# MCB-K64F-v1_0_0.net
KiCad netlist of a schematic drawn in EAGLE
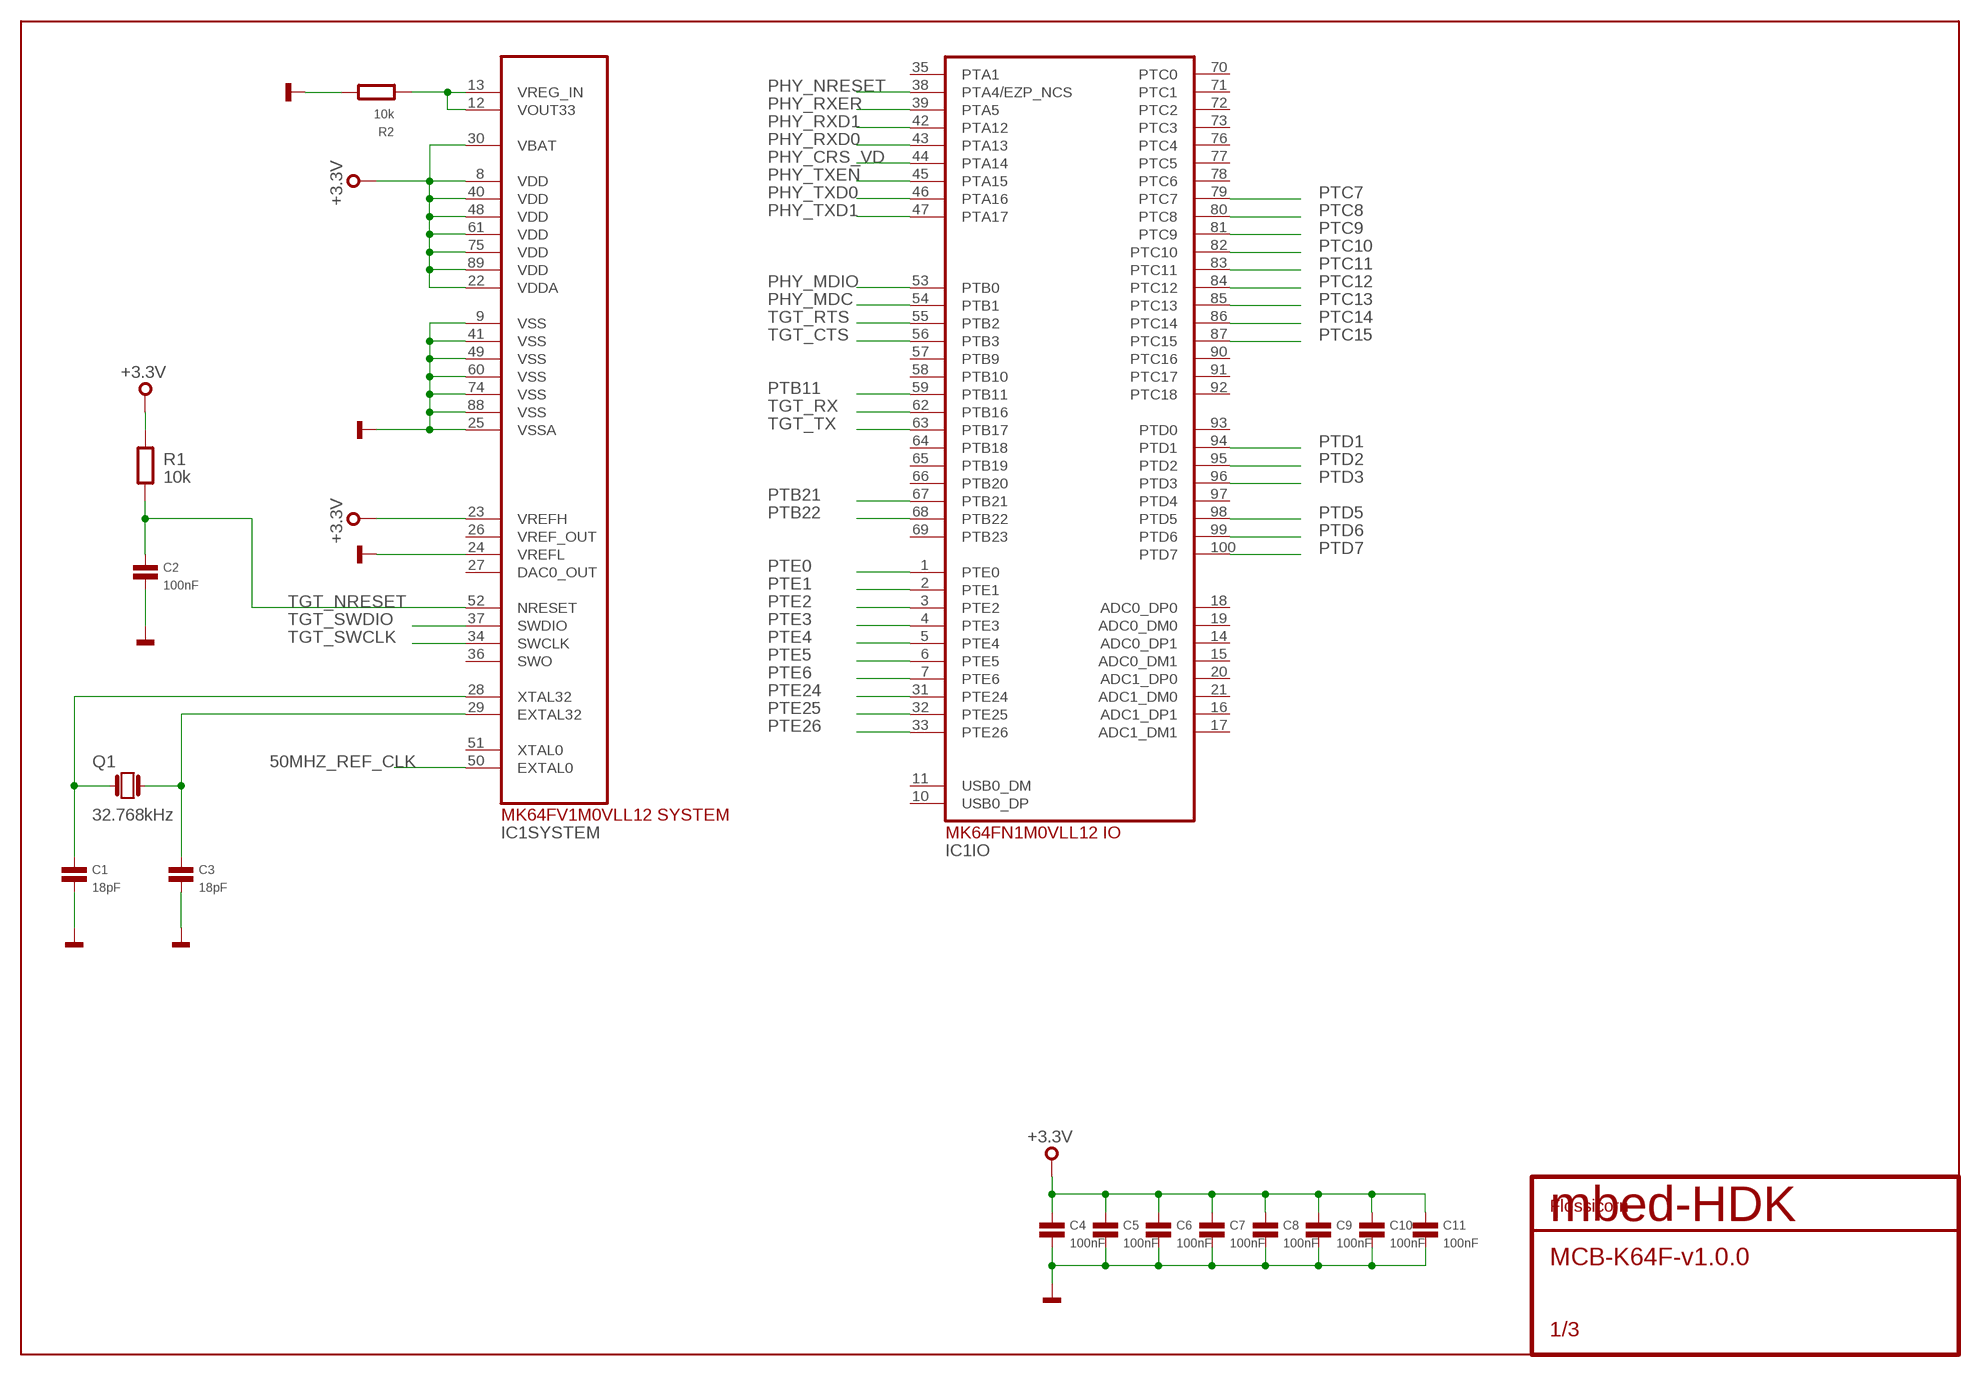
[diagram p0: schematic, sheet 1]
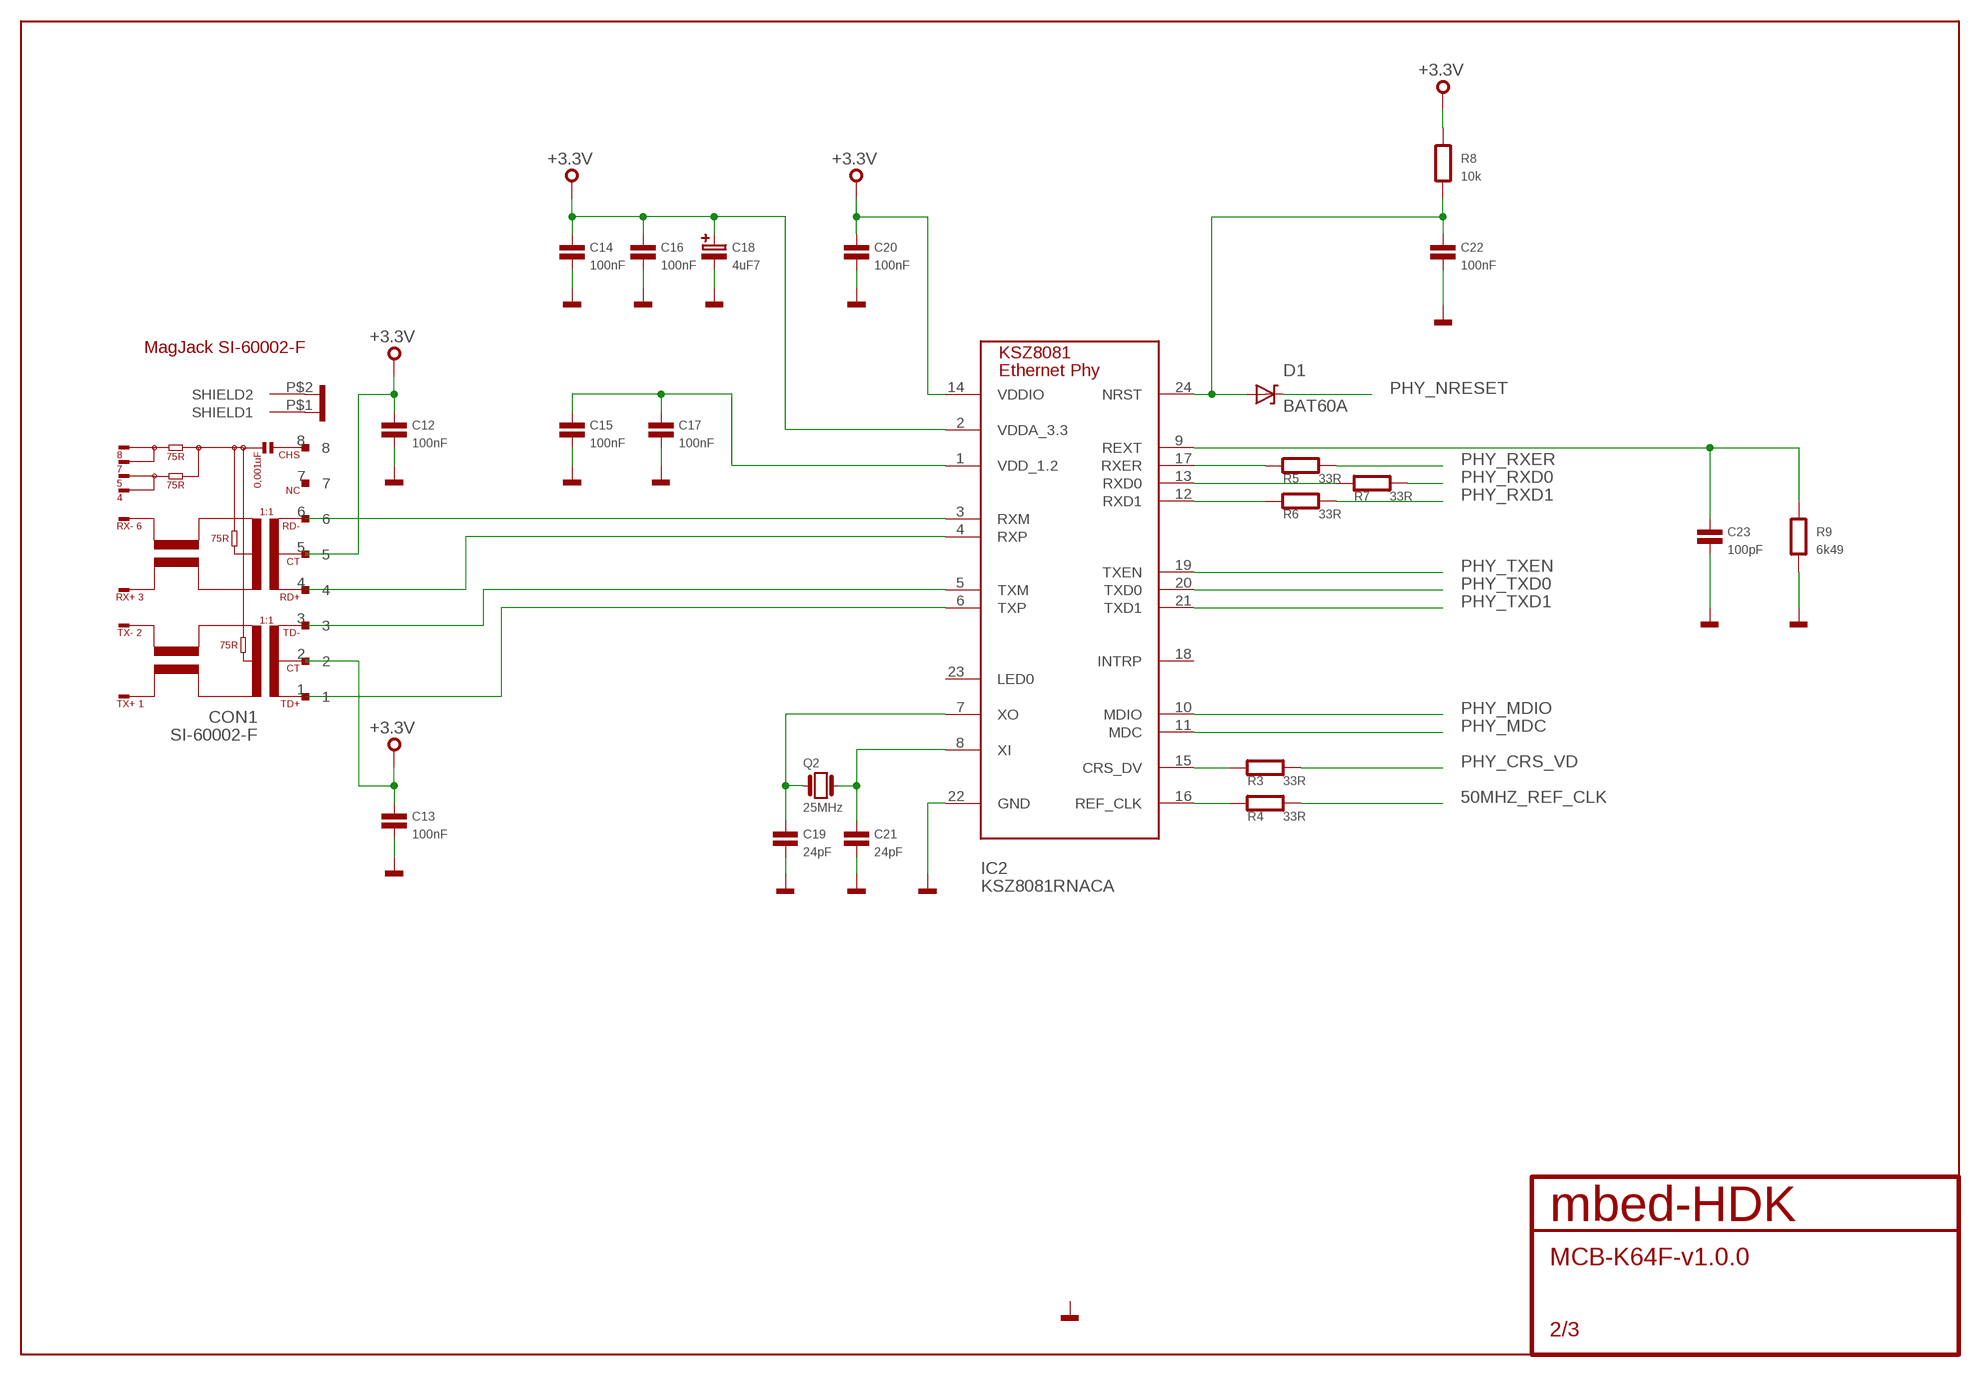
[diagram p1: schematic, sheet 2]
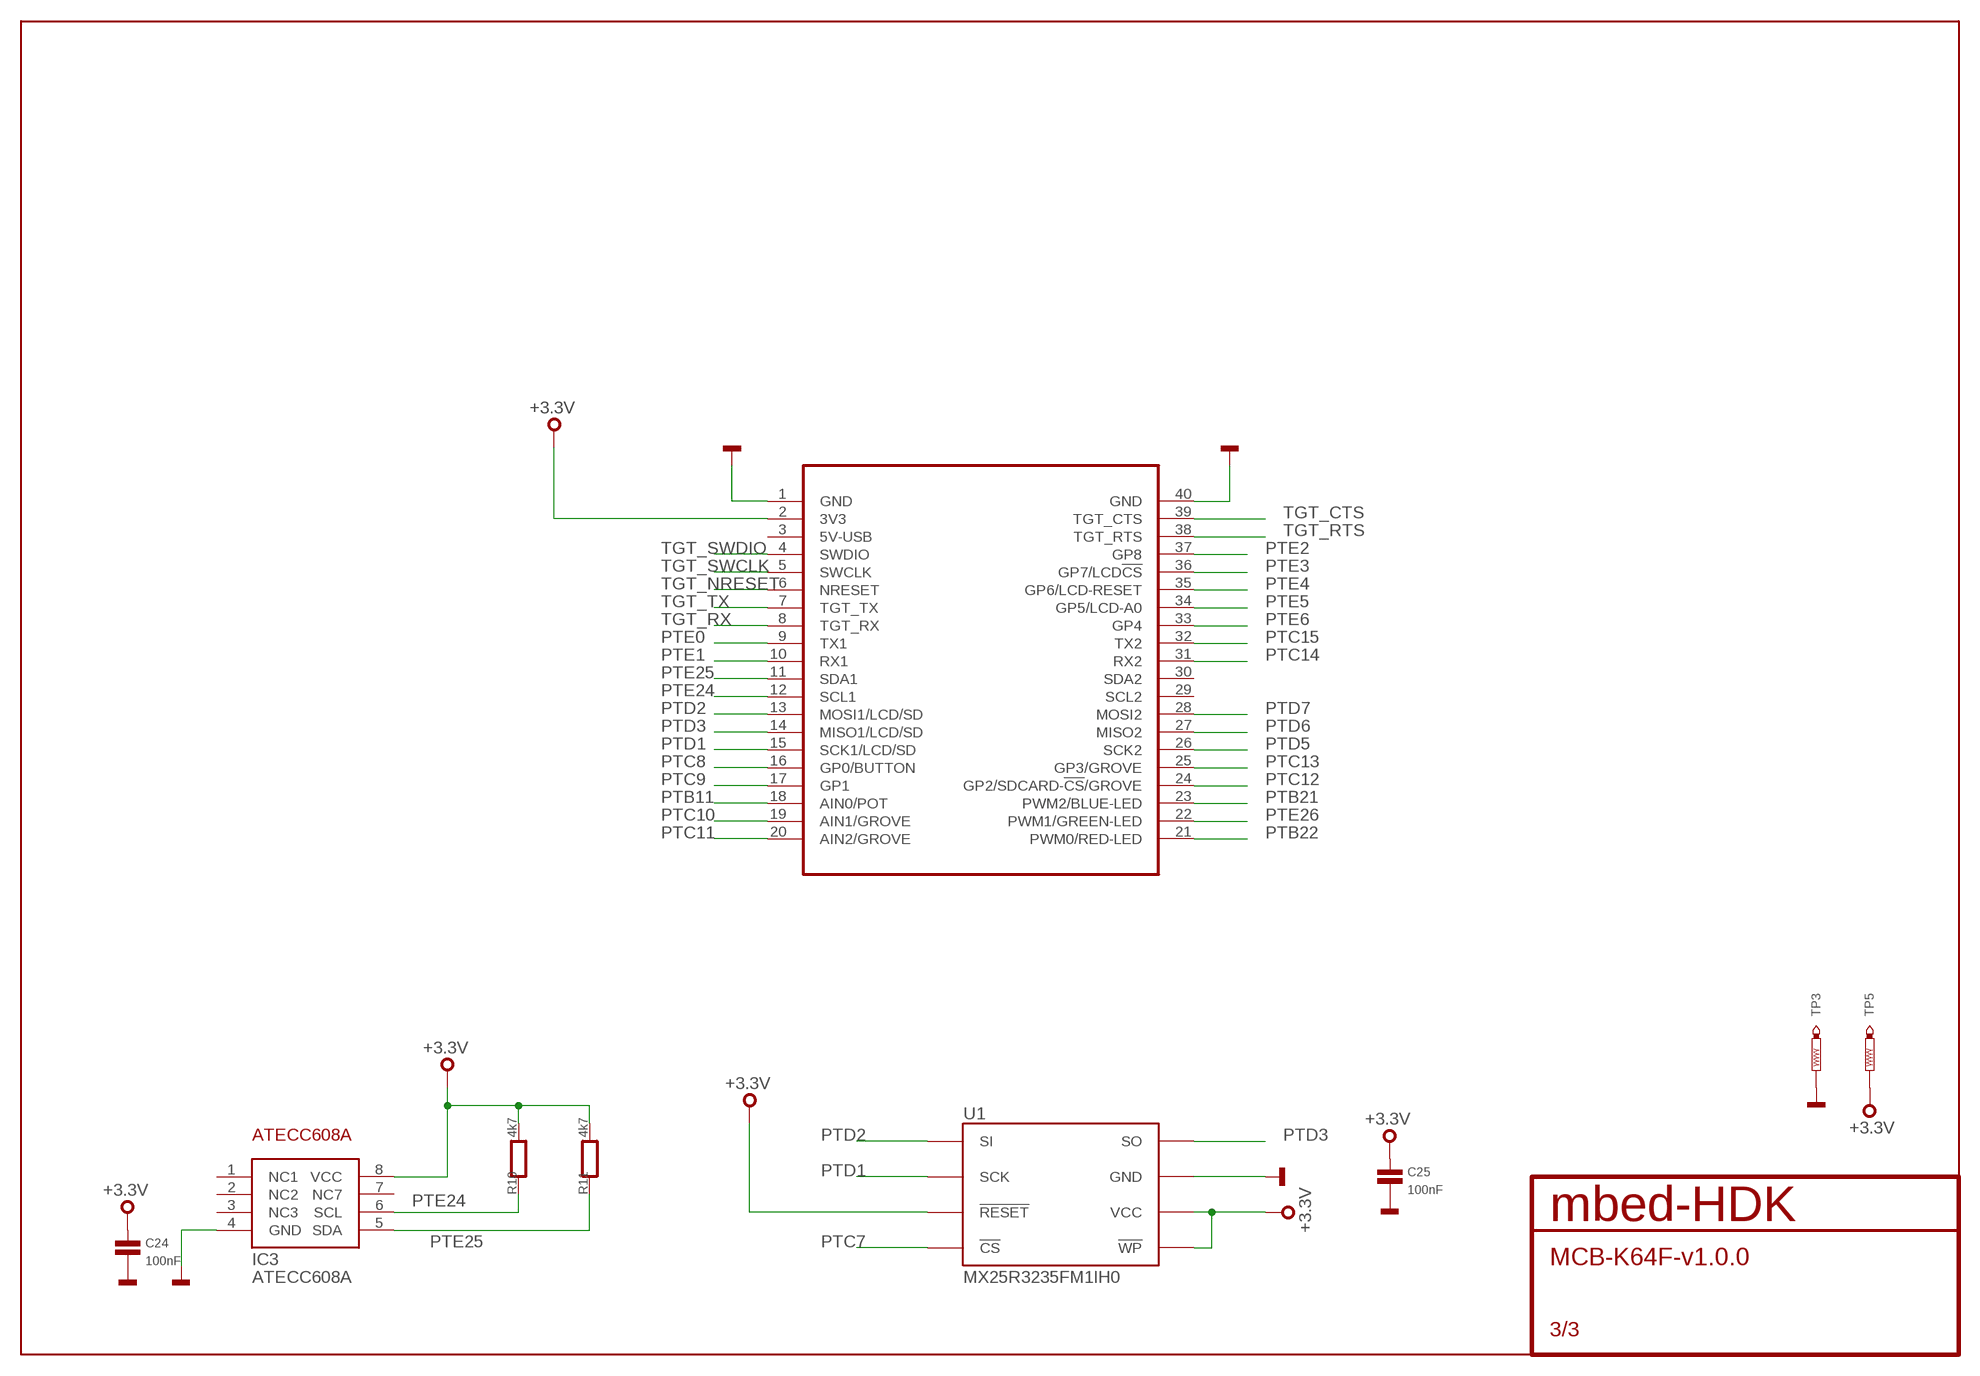
[diagram p2: schematic, sheet 3]

(export (version "E")
  (design (tool "Eeschema 10.0.6"))
  (components
    (comp (ref "C12")
      (value "100nF")
      (footprint "eagle-import:0603")
      (libsource (lib "eagle-import") (part "C0603"))
    )
    (comp (ref "C13")
      (value "100nF")
      (footprint "eagle-import:0603")
      (libsource (lib "eagle-import") (part "C0603"))
    )
    (comp (ref "C14")
      (value "100nF")
      (footprint "eagle-import:0603")
      (libsource (lib "eagle-import") (part "C0603"))
    )
    (comp (ref "C15")
      (value "100nF")
      (footprint "eagle-import:0603")
      (libsource (lib "eagle-import") (part "C0603"))
    )
    (comp (ref "C16")
      (value "100nF")
      (footprint "eagle-import:0603")
      (libsource (lib "eagle-import") (part "C0603"))
    )
    (comp (ref "C17")
      (value "100nF")
      (footprint "eagle-import:0603")
      (libsource (lib "eagle-import") (part "C0603"))
    )
    (comp (ref "C18")
      (value "4uF7")
      (footprint "eagle-import:SMC_A")
      (libsource (lib "eagle-import") (part "C-POLA"))
    )
    (comp (ref "C19")
      (value "24pF")
      (footprint "eagle-import:0603")
      (libsource (lib "eagle-import") (part "C0603"))
    )
    (comp (ref "C20")
      (value "100nF")
      (footprint "eagle-import:0603")
      (libsource (lib "eagle-import") (part "C0603"))
    )
    (comp (ref "C21")
      (value "24pF")
      (footprint "eagle-import:0603")
      (libsource (lib "eagle-import") (part "C0603"))
    )
    (comp (ref "C22")
      (value "100nF")
      (footprint "eagle-import:0603")
      (libsource (lib "eagle-import") (part "C0603"))
    )
    (comp (ref "C23")
      (value "100pF")
      (footprint "eagle-import:0603")
      (libsource (lib "eagle-import") (part "C0603"))
    )
    (comp (ref "CON1")
      (value "SI-60002-F")
      (footprint "eagle-import:RJ45")
      (fields (field (name "MF") "Stewart Connector"))
      (libsource (lib "eagle-import") (part "SI-60002-F"))
    )
    (comp (ref "D1")
      (value "BAT60A")
      (footprint "eagle-import:BAT60A")
      (libsource (lib "eagle-import") (part "BAT60A"))
    )
    (comp (ref "IC2")
      (value "KSZ8081RNACA")
      (footprint "eagle-import:QFN-24")
      (libsource (lib "eagle-import") (part "KSZ8081RNACA"))
    )
    (comp (ref "Q2")
      (value "25MHz")
      (footprint "eagle-import:3.2X.2.5")
      (libsource (lib "eagle-import") (part "Q_3.2X2.5"))
    )
    (comp (ref "R3")
      (value "33R")
      (footprint "eagle-import:0603")
      (libsource (lib "eagle-import") (part "R0603"))
    )
    (comp (ref "R4")
      (value "33R")
      (footprint "eagle-import:0603")
      (libsource (lib "eagle-import") (part "R0603"))
    )
    (comp (ref "R5")
      (value "33R")
      (footprint "eagle-import:0603")
      (libsource (lib "eagle-import") (part "R0603"))
    )
    (comp (ref "R6")
      (value "33R")
      (footprint "eagle-import:0603")
      (libsource (lib "eagle-import") (part "R0603"))
    )
    (comp (ref "R7")
      (value "33R")
      (footprint "eagle-import:0603")
      (libsource (lib "eagle-import") (part "R0603"))
    )
    (comp (ref "R8")
      (value "10k")
      (footprint "eagle-import:0603")
      (libsource (lib "eagle-import") (part "R0603"))
    )
    (comp (ref "R9")
      (value "6k49")
      (footprint "eagle-import:0603")
      (libsource (lib "eagle-import") (part "R0603"))
    )
    (comp (ref "C1")
      (value "18pF")
      (footprint "eagle-import:0603")
      (libsource (lib "eagle-import") (part "C0603"))
    )
    (comp (ref "C2")
      (value "100nF")
      (footprint "eagle-import:0603")
      (libsource (lib "eagle-import") (part "C0603"))
    )
    (comp (ref "C3")
      (value "18pF")
      (footprint "eagle-import:0603")
      (libsource (lib "eagle-import") (part "C0603"))
    )
    (comp (ref "C4")
      (value "100nF")
      (footprint "eagle-import:0603")
      (libsource (lib "eagle-import") (part "C0603"))
    )
    (comp (ref "C5")
      (value "100nF")
      (footprint "eagle-import:0603")
      (libsource (lib "eagle-import") (part "C0603"))
    )
    (comp (ref "C6")
      (value "100nF")
      (footprint "eagle-import:0603")
      (libsource (lib "eagle-import") (part "C0603"))
    )
    (comp (ref "C7")
      (value "100nF")
      (footprint "eagle-import:0603")
      (libsource (lib "eagle-import") (part "C0603"))
    )
    (comp (ref "C8")
      (value "100nF")
      (footprint "eagle-import:0603")
      (libsource (lib "eagle-import") (part "C0603"))
    )
    (comp (ref "C9")
      (value "100nF")
      (footprint "eagle-import:0603")
      (libsource (lib "eagle-import") (part "C0603"))
    )
    (comp (ref "C10")
      (value "100nF")
      (footprint "eagle-import:0603")
      (libsource (lib "eagle-import") (part "C0603"))
    )
    (comp (ref "C11")
      (value "100nF")
      (footprint "eagle-import:0603")
      (libsource (lib "eagle-import") (part "C0603"))
    )
    (comp (ref "IC1")
      (value "MK64FN1M0VLL12")
      (footprint "eagle-import:LQFP100")
      (libsource (lib "eagle-import") (part "MK64FN1M0VLL12"))
    )
    (comp (ref "Q1")
      (value "32.768kHz")
      (footprint "eagle-import:FC135")
      (libsource (lib "eagle-import") (part "Q_FC135"))
    )
    (comp (ref "R1")
      (value "10k")
      (footprint "eagle-import:0603")
      (libsource (lib "eagle-import") (part "R0603"))
    )
    (comp (ref "R2")
      (value "10k")
      (footprint "eagle-import:0603")
      (libsource (lib "eagle-import") (part "R0603"))
    )
    (comp (ref "SS1")
      (value "FLOSSICORN0.5")
      (footprint "eagle-import:FLOSSICORN-0.5")
      (libsource (lib "eagle-import") (part "FLOSSICORN0.5"))
    )
    (comp (ref "C24")
      (value "100nF")
      (footprint "eagle-import:0603")
      (libsource (lib "eagle-import") (part "CAPACITOR0603"))
    )
    (comp (ref "C25")
      (value "100nF")
      (footprint "eagle-import:0603")
      (libsource (lib "eagle-import") (part "CAPACITOR0603"))
    )
    (comp (ref "IC3")
      (value "ATECC608A")
      (footprint "eagle-import:SO8")
      (libsource (lib "eagle-import") (part "ATECC608A"))
    )
    (comp (ref "MOD1")
      (value "MODULE_DAUGHTER")
      (footprint "eagle-import:MODULE_DAUGHTER")
      (libsource (lib "eagle-import") (part "MODULE_DAUGHTER"))
    )
    (comp (ref "R10")
      (value "4k7")
      (footprint "eagle-import:0603")
      (libsource (lib "eagle-import") (part "RESISTOR0603"))
    )
    (comp (ref "R11")
      (value "4k7")
      (footprint "eagle-import:0603")
      (libsource (lib "eagle-import") (part "RESISTOR0603"))
    )
    (comp (ref "TP3")
      (value "TEST-POINT-50R-PTH")
      (footprint "eagle-import:TP50-PTH")
      (libsource (lib "eagle-import") (part "TEST-POINT-50R-PTH"))
    )
    (comp (ref "TP5")
      (value "TEST-POINT-50R-PTH")
      (footprint "eagle-import:TP50-PTH")
      (libsource (lib "eagle-import") (part "TEST-POINT-50R-PTH"))
    )
    (comp (ref "U1")
      (value "MX25R3235FM1IH0")
      (footprint "eagle-import:SO8")
      (fields (field (name "MF") "Macronix"))
      (libsource (lib "eagle-import") (part "MX25R3235FM1IH0"))
    )
  )
  (nets
    (net (code "1") (name "+3.3V") (class "Default")
      (node (ref "C10") (pin "1") (pinfunction "P$1_1") (pintype "passive"))
      (node (ref "C11") (pin "1") (pinfunction "P$1_1") (pintype "passive"))
      (node (ref "C12") (pin "1") (pinfunction "P$1_1") (pintype "passive"))
      (node (ref "C13") (pin "1") (pinfunction "P$1_1") (pintype "passive"))
      (node (ref "C14") (pin "1") (pinfunction "P$1_1") (pintype "passive"))
      (node (ref "C16") (pin "1") (pinfunction "P$1_1") (pintype "passive"))
      (node (ref "C18") (pin "+") (pinfunction "+_+") (pintype "passive"))
      (node (ref "C20") (pin "1") (pinfunction "P$1_1") (pintype "passive"))
      (node (ref "C24") (pin "1") (pinfunction "P$1_1") (pintype "passive"))
      (node (ref "C25") (pin "1") (pinfunction "P$1_1") (pintype "passive"))
      (node (ref "C4") (pin "1") (pinfunction "P$1_1") (pintype "passive"))
      (node (ref "C5") (pin "1") (pinfunction "P$1_1") (pintype "passive"))
      (node (ref "C6") (pin "1") (pinfunction "P$1_1") (pintype "passive"))
      (node (ref "C7") (pin "1") (pinfunction "P$1_1") (pintype "passive"))
      (node (ref "C8") (pin "1") (pinfunction "P$1_1") (pintype "passive"))
      (node (ref "C9") (pin "1") (pinfunction "P$1_1") (pintype "passive"))
      (node (ref "CON1") (pin "2") (pinfunction "2_2") (pintype "passive"))
      (node (ref "CON1") (pin "5") (pinfunction "5_5") (pintype "passive"))
      (node (ref "IC1") (pin "22") (pinfunction "VDDA_22") (pintype "bidirectional"))
      (node (ref "IC1") (pin "23") (pinfunction "VREFH_23") (pintype "bidirectional"))
      (node (ref "IC1") (pin "30") (pinfunction "VBAT_30") (pintype "bidirectional"))
      (node (ref "IC1") (pin "40") (pinfunction "VDD_40") (pintype "bidirectional"))
      (node (ref "IC1") (pin "48") (pinfunction "VDD_48") (pintype "bidirectional"))
      (node (ref "IC1") (pin "61") (pinfunction "VDD_61") (pintype "bidirectional"))
      (node (ref "IC1") (pin "75") (pinfunction "VDD_75") (pintype "bidirectional"))
      (node (ref "IC1") (pin "8") (pinfunction "VDD_8") (pintype "bidirectional"))
      (node (ref "IC1") (pin "89") (pinfunction "VDD_89") (pintype "bidirectional"))
      (node (ref "IC2") (pin "14") (pinfunction "VDDIO_14") (pintype "bidirectional"))
      (node (ref "IC2") (pin "2") (pinfunction "VDDA_3.3_2") (pintype "bidirectional"))
      (node (ref "IC3") (pin "8") (pinfunction "VCC_8") (pintype "bidirectional"))
      (node (ref "MOD1") (pin "2") (pinfunction "3V3_2") (pintype "bidirectional"))
      (node (ref "R1") (pin "2") (pinfunction "P$2_2") (pintype "passive"))
      (node (ref "R10") (pin "2") (pinfunction "P$2_2") (pintype "passive"))
      (node (ref "R11") (pin "2") (pinfunction "P$2_2") (pintype "passive"))
      (node (ref "R8") (pin "2") (pinfunction "P$2_2") (pintype "passive"))
      (node (ref "TP5") (pin "TP") (pinfunction "TP_TP") (pintype "input"))
      (node (ref "U1") (pin "3") (pinfunction "~{WP}_3") (pintype "bidirectional"))
      (node (ref "U1") (pin "7") (pinfunction "~{RESET}_7") (pintype "bidirectional"))
      (node (ref "U1") (pin "8") (pinfunction "VCC_8") (pintype "bidirectional"))
    )
    (net (code "2") (name "50MHZ_REF_CLK") (class "Default")
      (node (ref "IC1") (pin "50") (pinfunction "EXTAL0_50") (pintype "bidirectional"))
      (node (ref "R4") (pin "2") (pinfunction "P$2_2") (pintype "passive"))
    )
    (net (code "3") (name "GND") (class "Default")
      (node (ref "C1") (pin "2") (pinfunction "P$2_2") (pintype "passive"))
      (node (ref "C10") (pin "2") (pinfunction "P$2_2") (pintype "passive"))
      (node (ref "C11") (pin "2") (pinfunction "P$2_2") (pintype "passive"))
      (node (ref "C12") (pin "2") (pinfunction "P$2_2") (pintype "passive"))
      (node (ref "C13") (pin "2") (pinfunction "P$2_2") (pintype "passive"))
      (node (ref "C14") (pin "2") (pinfunction "P$2_2") (pintype "passive"))
      (node (ref "C15") (pin "2") (pinfunction "P$2_2") (pintype "passive"))
      (node (ref "C16") (pin "2") (pinfunction "P$2_2") (pintype "passive"))
      (node (ref "C17") (pin "2") (pinfunction "P$2_2") (pintype "passive"))
      (node (ref "C18") (pin "-") (pinfunction "-_-") (pintype "passive"))
      (node (ref "C19") (pin "2") (pinfunction "P$2_2") (pintype "passive"))
      (node (ref "C2") (pin "2") (pinfunction "P$2_2") (pintype "passive"))
      (node (ref "C20") (pin "2") (pinfunction "P$2_2") (pintype "passive"))
      (node (ref "C21") (pin "2") (pinfunction "P$2_2") (pintype "passive"))
      (node (ref "C22") (pin "2") (pinfunction "P$2_2") (pintype "passive"))
      (node (ref "C23") (pin "2") (pinfunction "P$2_2") (pintype "passive"))
      (node (ref "C24") (pin "2") (pinfunction "P$2_2") (pintype "passive"))
      (node (ref "C25") (pin "2") (pinfunction "P$2_2") (pintype "passive"))
      (node (ref "C3") (pin "2") (pinfunction "P$2_2") (pintype "passive"))
      (node (ref "C4") (pin "2") (pinfunction "P$2_2") (pintype "passive"))
      (node (ref "C5") (pin "2") (pinfunction "P$2_2") (pintype "passive"))
      (node (ref "C6") (pin "2") (pinfunction "P$2_2") (pintype "passive"))
      (node (ref "C7") (pin "2") (pinfunction "P$2_2") (pintype "passive"))
      (node (ref "C8") (pin "2") (pinfunction "P$2_2") (pintype "passive"))
      (node (ref "C9") (pin "2") (pinfunction "P$2_2") (pintype "passive"))
      (node (ref "CON1") (pin "P$1") (pinfunction "SHIELD1_P$1") (pintype "bidirectional"))
      (node (ref "CON1") (pin "P$2") (pinfunction "SHIELD2_P$2") (pintype "bidirectional"))
      (node (ref "IC1") (pin "24") (pinfunction "VREFL_24") (pintype "bidirectional"))
      (node (ref "IC1") (pin "25") (pinfunction "VSSA_25") (pintype "bidirectional"))
      (node (ref "IC1") (pin "41") (pinfunction "VSS_41") (pintype "bidirectional"))
      (node (ref "IC1") (pin "49") (pinfunction "VSS_49") (pintype "bidirectional"))
      (node (ref "IC1") (pin "60") (pinfunction "VSS_60") (pintype "bidirectional"))
      (node (ref "IC1") (pin "74") (pinfunction "VSS_74") (pintype "bidirectional"))
      (node (ref "IC1") (pin "88") (pinfunction "VSS_88") (pintype "bidirectional"))
      (node (ref "IC1") (pin "9") (pinfunction "VSS_9") (pintype "bidirectional"))
      (node (ref "IC2") (pin "22") (pinfunction "GND_22") (pintype "bidirectional"))
      (node (ref "IC3") (pin "4") (pinfunction "GND_4") (pintype "bidirectional"))
      (node (ref "MOD1") (pin "1") (pinfunction "GND_1") (pintype "bidirectional"))
      (node (ref "MOD1") (pin "40") (pinfunction "GND_40") (pintype "bidirectional"))
      (node (ref "R2") (pin "2") (pinfunction "P$2_2") (pintype "passive"))
      (node (ref "R9") (pin "1") (pinfunction "P$1_1") (pintype "passive"))
      (node (ref "TP3") (pin "TP") (pinfunction "TP_TP") (pintype "input"))
      (node (ref "U1") (pin "4") (pinfunction "GND_4") (pintype "bidirectional"))
    )
    (net (code "4") (name "Net-(C1-P$1)") (class "Default")
      (node (ref "C1") (pin "1") (pinfunction "P$1_1") (pintype "passive"))
      (node (ref "IC1") (pin "28") (pinfunction "XTAL32_28") (pintype "bidirectional"))
      (node (ref "Q1") (pin "X1") (pinfunction "1_X1") (pintype "passive"))
    )
    (net (code "5") (name "Net-(C3-P$1)") (class "Default")
      (node (ref "C3") (pin "1") (pinfunction "P$1_1") (pintype "passive"))
      (node (ref "IC1") (pin "29") (pinfunction "EXTAL32_29") (pintype "bidirectional"))
      (node (ref "Q1") (pin "X2") (pinfunction "2_X2") (pintype "passive"))
    )
    (net (code "6") (name "Net-(C15-P$1)") (class "Default")
      (node (ref "C15") (pin "1") (pinfunction "P$1_1") (pintype "passive"))
      (node (ref "C17") (pin "1") (pinfunction "P$1_1") (pintype "passive"))
      (node (ref "IC2") (pin "1") (pinfunction "VDD_1.2_1") (pintype "bidirectional"))
    )
    (net (code "7") (name "Net-(C19-P$1)") (class "Default")
      (node (ref "C19") (pin "1") (pinfunction "P$1_1") (pintype "passive"))
      (node (ref "IC2") (pin "7") (pinfunction "XO_7") (pintype "bidirectional"))
      (node (ref "Q2") (pin "P$1") (pinfunction "1_P$1") (pintype "passive"))
    )
    (net (code "8") (name "Net-(C21-P$1)") (class "Default")
      (node (ref "C21") (pin "1") (pinfunction "P$1_1") (pintype "passive"))
      (node (ref "IC2") (pin "8") (pinfunction "XI_8") (pintype "bidirectional"))
      (node (ref "Q2") (pin "P$3") (pinfunction "2_P$3") (pintype "passive"))
    )
    (net (code "9") (name "Net-(C22-P$1)") (class "Default")
      (node (ref "C22") (pin "1") (pinfunction "P$1_1") (pintype "passive"))
      (node (ref "D1") (pin "A") (pinfunction "A_A") (pintype "passive"))
      (node (ref "IC2") (pin "24") (pinfunction "NRST_24") (pintype "bidirectional"))
      (node (ref "R8") (pin "1") (pinfunction "P$1_1") (pintype "passive"))
    )
    (net (code "10") (name "Net-(C23-P$1)") (class "Default")
      (node (ref "C23") (pin "1") (pinfunction "P$1_1") (pintype "passive"))
      (node (ref "IC2") (pin "9") (pinfunction "REXT_9") (pintype "bidirectional"))
      (node (ref "R9") (pin "2") (pinfunction "P$2_2") (pintype "passive"))
    )
    (net (code "11") (name "Net-(IC1B-VOUT33)") (class "Default")
      (node (ref "IC1") (pin "12") (pinfunction "VOUT33_12") (pintype "bidirectional"))
      (node (ref "IC1") (pin "13") (pinfunction "VREG_IN_13") (pintype "bidirectional"))
      (node (ref "R2") (pin "1") (pinfunction "P$1_1") (pintype "passive"))
    )
    (net (code "12") (name "Net-(IC2-CRS_DV)") (class "Default")
      (node (ref "IC2") (pin "15") (pinfunction "CRS_DV_15") (pintype "bidirectional"))
      (node (ref "R3") (pin "1") (pinfunction "P$1_1") (pintype "passive"))
    )
    (net (code "13") (name "Net-(IC2-REF_CLK)") (class "Default")
      (node (ref "IC2") (pin "16") (pinfunction "REF_CLK_16") (pintype "bidirectional"))
      (node (ref "R4") (pin "1") (pinfunction "P$1_1") (pintype "passive"))
    )
    (net (code "14") (name "Net-(IC2-RXD0)") (class "Default")
      (node (ref "IC2") (pin "13") (pinfunction "RXD0_13") (pintype "bidirectional"))
      (node (ref "R7") (pin "1") (pinfunction "P$1_1") (pintype "passive"))
    )
    (net (code "15") (name "Net-(IC2-RXD1)") (class "Default")
      (node (ref "IC2") (pin "12") (pinfunction "RXD1_12") (pintype "bidirectional"))
      (node (ref "R6") (pin "1") (pinfunction "P$1_1") (pintype "passive"))
    )
    (net (code "16") (name "Net-(IC2-RXER)") (class "Default")
      (node (ref "IC2") (pin "17") (pinfunction "RXER_17") (pintype "bidirectional"))
      (node (ref "R5") (pin "1") (pinfunction "P$1_1") (pintype "passive"))
    )
    (net (code "17") (name "Net-(IC2-RXM)") (class "Default")
      (node (ref "CON1") (pin "6") (pinfunction "6_6") (pintype "passive"))
      (node (ref "IC2") (pin "3") (pinfunction "RXM_3") (pintype "bidirectional"))
    )
    (net (code "18") (name "Net-(IC2-RXP)") (class "Default")
      (node (ref "CON1") (pin "4") (pinfunction "4_4") (pintype "passive"))
      (node (ref "IC2") (pin "4") (pinfunction "RXP_4") (pintype "bidirectional"))
    )
    (net (code "19") (name "Net-(IC2-TXM)") (class "Default")
      (node (ref "CON1") (pin "3") (pinfunction "3_3") (pintype "passive"))
      (node (ref "IC2") (pin "5") (pinfunction "TXM_5") (pintype "bidirectional"))
    )
    (net (code "20") (name "Net-(IC2-TXP)") (class "Default")
      (node (ref "CON1") (pin "1") (pinfunction "1_1") (pintype "passive"))
      (node (ref "IC2") (pin "6") (pinfunction "TXP_6") (pintype "bidirectional"))
    )
    (net (code "21") (name "PHY_CRS_VD") (class "Default")
      (node (ref "IC1") (pin "44") (pinfunction "PTA14_44") (pintype "bidirectional"))
      (node (ref "R3") (pin "2") (pinfunction "P$2_2") (pintype "passive"))
    )
    (net (code "22") (name "PHY_MDC") (class "Default")
      (node (ref "IC1") (pin "54") (pinfunction "PTB1_54") (pintype "bidirectional"))
      (node (ref "IC2") (pin "11") (pinfunction "MDC_11") (pintype "bidirectional"))
    )
    (net (code "23") (name "PHY_MDIO") (class "Default")
      (node (ref "IC1") (pin "53") (pinfunction "PTB0_53") (pintype "bidirectional"))
      (node (ref "IC2") (pin "10") (pinfunction "MDIO_10") (pintype "bidirectional"))
    )
    (net (code "24") (name "PHY_NRESET") (class "Default")
      (node (ref "D1") (pin "K") (pinfunction "K_K") (pintype "passive"))
      (node (ref "IC1") (pin "38") (pinfunction "PTA4/EZP_NCS_38") (pintype "bidirectional"))
    )
    (net (code "25") (name "PHY_RXD0") (class "Default")
      (node (ref "IC1") (pin "43") (pinfunction "PTA13_43") (pintype "bidirectional"))
      (node (ref "R7") (pin "2") (pinfunction "P$2_2") (pintype "passive"))
    )
    (net (code "26") (name "PHY_RXD1") (class "Default")
      (node (ref "IC1") (pin "42") (pinfunction "PTA12_42") (pintype "bidirectional"))
      (node (ref "R6") (pin "2") (pinfunction "P$2_2") (pintype "passive"))
    )
    (net (code "27") (name "PHY_RXER") (class "Default")
      (node (ref "IC1") (pin "39") (pinfunction "PTA5_39") (pintype "bidirectional"))
      (node (ref "R5") (pin "2") (pinfunction "P$2_2") (pintype "passive"))
    )
    (net (code "28") (name "PHY_TXD0") (class "Default")
      (node (ref "IC1") (pin "46") (pinfunction "PTA16_46") (pintype "bidirectional"))
      (node (ref "IC2") (pin "20") (pinfunction "TXD0_20") (pintype "bidirectional"))
    )
    (net (code "29") (name "PHY_TXD1") (class "Default")
      (node (ref "IC1") (pin "47") (pinfunction "PTA17_47") (pintype "bidirectional"))
      (node (ref "IC2") (pin "21") (pinfunction "TXD1_21") (pintype "bidirectional"))
    )
    (net (code "30") (name "PHY_TXEN") (class "Default")
      (node (ref "IC1") (pin "45") (pinfunction "PTA15_45") (pintype "bidirectional"))
      (node (ref "IC2") (pin "19") (pinfunction "TXEN_19") (pintype "bidirectional"))
    )
    (net (code "31") (name "PTB11") (class "Default")
      (node (ref "IC1") (pin "59") (pinfunction "PTB11_59") (pintype "bidirectional"))
      (node (ref "MOD1") (pin "18") (pinfunction "AIN0/POT_18") (pintype "bidirectional"))
    )
    (net (code "32") (name "PTB21") (class "Default")
      (node (ref "IC1") (pin "67") (pinfunction "PTB21_67") (pintype "bidirectional"))
      (node (ref "MOD1") (pin "23") (pinfunction "PWM2/BLUE-LED_23") (pintype "bidirectional"))
    )
    (net (code "33") (name "PTB22") (class "Default")
      (node (ref "IC1") (pin "68") (pinfunction "PTB22_68") (pintype "bidirectional"))
      (node (ref "MOD1") (pin "21") (pinfunction "PWM0/RED-LED_21") (pintype "bidirectional"))
    )
    (net (code "34") (name "PTC7") (class "Default")
      (node (ref "IC1") (pin "79") (pinfunction "PTC7_79") (pintype "bidirectional"))
      (node (ref "U1") (pin "1") (pinfunction "~{CS}_1") (pintype "bidirectional"))
    )
    (net (code "35") (name "PTC8") (class "Default")
      (node (ref "IC1") (pin "80") (pinfunction "PTC8_80") (pintype "bidirectional"))
      (node (ref "MOD1") (pin "16") (pinfunction "GP0/BUTTON_16") (pintype "bidirectional"))
    )
    (net (code "36") (name "PTC9") (class "Default")
      (node (ref "IC1") (pin "81") (pinfunction "PTC9_81") (pintype "bidirectional"))
      (node (ref "MOD1") (pin "17") (pinfunction "GP1_17") (pintype "bidirectional"))
    )
    (net (code "37") (name "PTC10") (class "Default")
      (node (ref "IC1") (pin "82") (pinfunction "PTC10_82") (pintype "bidirectional"))
      (node (ref "MOD1") (pin "19") (pinfunction "AIN1/GROVE_19") (pintype "bidirectional"))
    )
    (net (code "38") (name "PTC11") (class "Default")
      (node (ref "IC1") (pin "83") (pinfunction "PTC11_83") (pintype "bidirectional"))
      (node (ref "MOD1") (pin "20") (pinfunction "AIN2/GROVE_20") (pintype "bidirectional"))
    )
    (net (code "39") (name "PTC12") (class "Default")
      (node (ref "IC1") (pin "84") (pinfunction "PTC12_84") (pintype "bidirectional"))
      (node (ref "MOD1") (pin "24") (pinfunction "GP2/SDCARD-~{CS}/GROVE_24") (pintype "bidirectional"))
    )
    (net (code "40") (name "PTC13") (class "Default")
      (node (ref "IC1") (pin "85") (pinfunction "PTC13_85") (pintype "bidirectional"))
      (node (ref "MOD1") (pin "25") (pinfunction "GP3/GROVE_25") (pintype "bidirectional"))
    )
    (net (code "41") (name "PTC14") (class "Default")
      (node (ref "IC1") (pin "86") (pinfunction "PTC14_86") (pintype "bidirectional"))
      (node (ref "MOD1") (pin "31") (pinfunction "RX2_31") (pintype "bidirectional"))
    )
    (net (code "42") (name "PTC15") (class "Default")
      (node (ref "IC1") (pin "87") (pinfunction "PTC15_87") (pintype "bidirectional"))
      (node (ref "MOD1") (pin "32") (pinfunction "TX2_32") (pintype "bidirectional"))
    )
    (net (code "43") (name "PTD1") (class "Default")
      (node (ref "IC1") (pin "94") (pinfunction "PTD1_94") (pintype "bidirectional"))
      (node (ref "MOD1") (pin "15") (pinfunction "SCK1/LCD/SD_15") (pintype "bidirectional"))
      (node (ref "U1") (pin "6") (pinfunction "SCK_6") (pintype "bidirectional"))
    )
    (net (code "44") (name "PTD2") (class "Default")
      (node (ref "IC1") (pin "95") (pinfunction "PTD2_95") (pintype "bidirectional"))
      (node (ref "MOD1") (pin "13") (pinfunction "MOSI1/LCD/SD_13") (pintype "bidirectional"))
      (node (ref "U1") (pin "5") (pinfunction "SI_5") (pintype "bidirectional"))
    )
    (net (code "45") (name "PTD3") (class "Default")
      (node (ref "IC1") (pin "96") (pinfunction "PTD3_96") (pintype "bidirectional"))
      (node (ref "MOD1") (pin "14") (pinfunction "MISO1/LCD/SD_14") (pintype "bidirectional"))
      (node (ref "U1") (pin "2") (pinfunction "SO_2") (pintype "bidirectional"))
    )
    (net (code "46") (name "PTD5") (class "Default")
      (node (ref "IC1") (pin "98") (pinfunction "PTD5_98") (pintype "bidirectional"))
      (node (ref "MOD1") (pin "26") (pinfunction "SCK2_26") (pintype "bidirectional"))
    )
    (net (code "47") (name "PTD6") (class "Default")
      (node (ref "IC1") (pin "99") (pinfunction "PTD6_99") (pintype "bidirectional"))
      (node (ref "MOD1") (pin "27") (pinfunction "MISO2_27") (pintype "bidirectional"))
    )
    (net (code "48") (name "PTD7") (class "Default")
      (node (ref "IC1") (pin "100") (pinfunction "PTD7_100") (pintype "bidirectional"))
      (node (ref "MOD1") (pin "28") (pinfunction "MOSI2_28") (pintype "bidirectional"))
    )
    (net (code "49") (name "PTE0") (class "Default")
      (node (ref "IC1") (pin "1") (pinfunction "PTE0_1") (pintype "bidirectional"))
      (node (ref "MOD1") (pin "9") (pinfunction "TX1_9") (pintype "bidirectional"))
    )
    (net (code "50") (name "PTE1") (class "Default")
      (node (ref "IC1") (pin "2") (pinfunction "PTE1_2") (pintype "bidirectional"))
      (node (ref "MOD1") (pin "10") (pinfunction "RX1_10") (pintype "bidirectional"))
    )
    (net (code "51") (name "PTE2") (class "Default")
      (node (ref "IC1") (pin "3") (pinfunction "PTE2_3") (pintype "bidirectional"))
      (node (ref "MOD1") (pin "37") (pinfunction "GP8_37") (pintype "bidirectional"))
    )
    (net (code "52") (name "PTE3") (class "Default")
      (node (ref "IC1") (pin "4") (pinfunction "PTE3_4") (pintype "bidirectional"))
      (node (ref "MOD1") (pin "36") (pinfunction "GP7/LCD~{CS}_36") (pintype "bidirectional"))
    )
    (net (code "53") (name "PTE4") (class "Default")
      (node (ref "IC1") (pin "5") (pinfunction "PTE4_5") (pintype "bidirectional"))
      (node (ref "MOD1") (pin "35") (pinfunction "GP6/LCD-RESET_35") (pintype "bidirectional"))
    )
    (net (code "54") (name "PTE5") (class "Default")
      (node (ref "IC1") (pin "6") (pinfunction "PTE5_6") (pintype "bidirectional"))
      (node (ref "MOD1") (pin "34") (pinfunction "GP5/LCD-A0_34") (pintype "bidirectional"))
    )
    (net (code "55") (name "PTE6") (class "Default")
      (node (ref "IC1") (pin "7") (pinfunction "PTE6_7") (pintype "bidirectional"))
      (node (ref "MOD1") (pin "33") (pinfunction "GP4_33") (pintype "bidirectional"))
    )
    (net (code "56") (name "PTE24") (class "Default")
      (node (ref "IC1") (pin "31") (pinfunction "PTE24_31") (pintype "bidirectional"))
      (node (ref "IC3") (pin "6") (pinfunction "SCL_6") (pintype "bidirectional"))
      (node (ref "MOD1") (pin "12") (pinfunction "SCL1_12") (pintype "bidirectional"))
      (node (ref "R10") (pin "1") (pinfunction "P$1_1") (pintype "passive"))
    )
    (net (code "57") (name "PTE25") (class "Default")
      (node (ref "IC1") (pin "32") (pinfunction "PTE25_32") (pintype "bidirectional"))
      (node (ref "IC3") (pin "5") (pinfunction "SDA_5") (pintype "bidirectional"))
      (node (ref "MOD1") (pin "11") (pinfunction "SDA1_11") (pintype "bidirectional"))
      (node (ref "R11") (pin "1") (pinfunction "P$1_1") (pintype "passive"))
    )
    (net (code "58") (name "PTE26") (class "Default")
      (node (ref "IC1") (pin "33") (pinfunction "PTE26_33") (pintype "bidirectional"))
      (node (ref "MOD1") (pin "22") (pinfunction "PWM1/GREEN-LED_22") (pintype "bidirectional"))
    )
    (net (code "59") (name "TGT_CTS") (class "Default")
      (node (ref "IC1") (pin "56") (pinfunction "PTB3_56") (pintype "bidirectional"))
      (node (ref "MOD1") (pin "39") (pinfunction "TGT_CTS_39") (pintype "bidirectional"))
    )
    (net (code "60") (name "TGT_NRESET") (class "Default")
      (node (ref "C2") (pin "1") (pinfunction "P$1_1") (pintype "passive"))
      (node (ref "IC1") (pin "52") (pinfunction "NRESET_52") (pintype "bidirectional"))
      (node (ref "MOD1") (pin "6") (pinfunction "NRESET_6") (pintype "bidirectional"))
      (node (ref "R1") (pin "1") (pinfunction "P$1_1") (pintype "passive"))
    )
    (net (code "61") (name "TGT_RTS") (class "Default")
      (node (ref "IC1") (pin "55") (pinfunction "PTB2_55") (pintype "bidirectional"))
      (node (ref "MOD1") (pin "38") (pinfunction "TGT_RTS_38") (pintype "bidirectional"))
    )
    (net (code "62") (name "TGT_RX") (class "Default")
      (node (ref "IC1") (pin "62") (pinfunction "PTB16_62") (pintype "bidirectional"))
      (node (ref "MOD1") (pin "8") (pinfunction "TGT_RX_8") (pintype "bidirectional"))
    )
    (net (code "63") (name "TGT_SWCLK") (class "Default")
      (node (ref "IC1") (pin "34") (pinfunction "SWCLK_34") (pintype "bidirectional"))
      (node (ref "MOD1") (pin "5") (pinfunction "SWCLK_5") (pintype "bidirectional"))
    )
    (net (code "64") (name "TGT_SWDIO") (class "Default")
      (node (ref "IC1") (pin "37") (pinfunction "SWDIO_37") (pintype "bidirectional"))
      (node (ref "MOD1") (pin "4") (pinfunction "SWDIO_4") (pintype "bidirectional"))
    )
    (net (code "65") (name "TGT_TX") (class "Default")
      (node (ref "IC1") (pin "63") (pinfunction "PTB17_63") (pintype "bidirectional"))
      (node (ref "MOD1") (pin "7") (pinfunction "TGT_TX_7") (pintype "bidirectional"))
    )
    (net (code "66") (name "unconnected-(CON1-Pad7)") (class "Default")
      (node (ref "CON1") (pin "7") (pinfunction "7_7") (pintype "passive"))
    )
    (net (code "67") (name "unconnected-(CON1-Pad8)") (class "Default")
      (node (ref "CON1") (pin "8") (pinfunction "8_8") (pintype "passive"))
    )
    (net (code "68") (name "unconnected-(IC1A-ADC0_DM0-Pad19)") (class "Default")
      (node (ref "IC1") (pin "19") (pinfunction "ADC0_DM0_19") (pintype "bidirectional"))
    )
    (net (code "69") (name "unconnected-(IC1A-ADC0_DM1-Pad15)") (class "Default")
      (node (ref "IC1") (pin "15") (pinfunction "ADC0_DM1_15") (pintype "bidirectional"))
    )
    (net (code "70") (name "unconnected-(IC1A-ADC0_DP0-Pad18)") (class "Default")
      (node (ref "IC1") (pin "18") (pinfunction "ADC0_DP0_18") (pintype "bidirectional"))
    )
    (net (code "71") (name "unconnected-(IC1A-ADC0_DP1-Pad14)") (class "Default")
      (node (ref "IC1") (pin "14") (pinfunction "ADC0_DP1_14") (pintype "bidirectional"))
    )
    (net (code "72") (name "unconnected-(IC1A-ADC1_DM0-Pad21)") (class "Default")
      (node (ref "IC1") (pin "21") (pinfunction "ADC1_DM0_21") (pintype "bidirectional"))
    )
    (net (code "73") (name "unconnected-(IC1A-ADC1_DM1-Pad17)") (class "Default")
      (node (ref "IC1") (pin "17") (pinfunction "ADC1_DM1_17") (pintype "bidirectional"))
    )
    (net (code "74") (name "unconnected-(IC1A-ADC1_DP0-Pad20)") (class "Default")
      (node (ref "IC1") (pin "20") (pinfunction "ADC1_DP0_20") (pintype "bidirectional"))
    )
    (net (code "75") (name "unconnected-(IC1A-ADC1_DP1-Pad16)") (class "Default")
      (node (ref "IC1") (pin "16") (pinfunction "ADC1_DP1_16") (pintype "bidirectional"))
    )
    (net (code "76") (name "unconnected-(IC1A-PTA1-Pad35)") (class "Default")
      (node (ref "IC1") (pin "35") (pinfunction "PTA1_35") (pintype "bidirectional"))
    )
    (net (code "77") (name "unconnected-(IC1A-PTB9-Pad57)") (class "Default")
      (node (ref "IC1") (pin "57") (pinfunction "PTB9_57") (pintype "bidirectional"))
    )
    (net (code "78") (name "unconnected-(IC1A-PTB10-Pad58)") (class "Default")
      (node (ref "IC1") (pin "58") (pinfunction "PTB10_58") (pintype "bidirectional"))
    )
    (net (code "79") (name "unconnected-(IC1A-PTB18-Pad64)") (class "Default")
      (node (ref "IC1") (pin "64") (pinfunction "PTB18_64") (pintype "bidirectional"))
    )
    (net (code "80") (name "unconnected-(IC1A-PTB19-Pad65)") (class "Default")
      (node (ref "IC1") (pin "65") (pinfunction "PTB19_65") (pintype "bidirectional"))
    )
    (net (code "81") (name "unconnected-(IC1A-PTB20-Pad66)") (class "Default")
      (node (ref "IC1") (pin "66") (pinfunction "PTB20_66") (pintype "bidirectional"))
    )
    (net (code "82") (name "unconnected-(IC1A-PTB23-Pad69)") (class "Default")
      (node (ref "IC1") (pin "69") (pinfunction "PTB23_69") (pintype "bidirectional"))
    )
    (net (code "83") (name "unconnected-(IC1A-PTC0-Pad70)") (class "Default")
      (node (ref "IC1") (pin "70") (pinfunction "PTC0_70") (pintype "bidirectional"))
    )
    (net (code "84") (name "unconnected-(IC1A-PTC1-Pad71)") (class "Default")
      (node (ref "IC1") (pin "71") (pinfunction "PTC1_71") (pintype "bidirectional"))
    )
    (net (code "85") (name "unconnected-(IC1A-PTC2-Pad72)") (class "Default")
      (node (ref "IC1") (pin "72") (pinfunction "PTC2_72") (pintype "bidirectional"))
    )
    (net (code "86") (name "unconnected-(IC1A-PTC3-Pad73)") (class "Default")
      (node (ref "IC1") (pin "73") (pinfunction "PTC3_73") (pintype "bidirectional"))
    )
    (net (code "87") (name "unconnected-(IC1A-PTC4-Pad76)") (class "Default")
      (node (ref "IC1") (pin "76") (pinfunction "PTC4_76") (pintype "bidirectional"))
    )
    (net (code "88") (name "unconnected-(IC1A-PTC5-Pad77)") (class "Default")
      (node (ref "IC1") (pin "77") (pinfunction "PTC5_77") (pintype "bidirectional"))
    )
    (net (code "89") (name "unconnected-(IC1A-PTC6-Pad78)") (class "Default")
      (node (ref "IC1") (pin "78") (pinfunction "PTC6_78") (pintype "bidirectional"))
    )
    (net (code "90") (name "unconnected-(IC1A-PTC16-Pad90)") (class "Default")
      (node (ref "IC1") (pin "90") (pinfunction "PTC16_90") (pintype "bidirectional"))
    )
    (net (code "91") (name "unconnected-(IC1A-PTC17-Pad91)") (class "Default")
      (node (ref "IC1") (pin "91") (pinfunction "PTC17_91") (pintype "bidirectional"))
    )
    (net (code "92") (name "unconnected-(IC1A-PTC18-Pad92)") (class "Default")
      (node (ref "IC1") (pin "92") (pinfunction "PTC18_92") (pintype "bidirectional"))
    )
    (net (code "93") (name "unconnected-(IC1A-PTD0-Pad93)") (class "Default")
      (node (ref "IC1") (pin "93") (pinfunction "PTD0_93") (pintype "bidirectional"))
    )
    (net (code "94") (name "unconnected-(IC1A-PTD4-Pad97)") (class "Default")
      (node (ref "IC1") (pin "97") (pinfunction "PTD4_97") (pintype "bidirectional"))
    )
    (net (code "95") (name "unconnected-(IC1A-USB0_DM-Pad11)") (class "Default")
      (node (ref "IC1") (pin "11") (pinfunction "USB0_DM_11") (pintype "bidirectional"))
    )
    (net (code "96") (name "unconnected-(IC1A-USB0_DP-Pad10)") (class "Default")
      (node (ref "IC1") (pin "10") (pinfunction "USB0_DP_10") (pintype "bidirectional"))
    )
    (net (code "97") (name "unconnected-(IC1B-DAC0_OUT-Pad27)") (class "Default")
      (node (ref "IC1") (pin "27") (pinfunction "DAC0_OUT_27") (pintype "bidirectional"))
    )
    (net (code "98") (name "unconnected-(IC1B-SWO-Pad36)") (class "Default")
      (node (ref "IC1") (pin "36") (pinfunction "SWO_36") (pintype "bidirectional"))
    )
    (net (code "99") (name "unconnected-(IC1B-VREF_OUT-Pad26)") (class "Default")
      (node (ref "IC1") (pin "26") (pinfunction "VREF_OUT_26") (pintype "bidirectional"))
    )
    (net (code "100") (name "unconnected-(IC1B-XTAL0-Pad51)") (class "Default")
      (node (ref "IC1") (pin "51") (pinfunction "XTAL0_51") (pintype "bidirectional"))
    )
    (net (code "101") (name "unconnected-(IC2-INTRP-Pad18)") (class "Default")
      (node (ref "IC2") (pin "18") (pinfunction "INTRP_18") (pintype "bidirectional"))
    )
    (net (code "102") (name "unconnected-(IC2-LED0-Pad23)") (class "Default")
      (node (ref "IC2") (pin "23") (pinfunction "LED0_23") (pintype "bidirectional"))
    )
    (net (code "103") (name "unconnected-(IC3-NC1-Pad1)") (class "Default")
      (node (ref "IC3") (pin "1") (pinfunction "NC1_1") (pintype "bidirectional"))
    )
    (net (code "104") (name "unconnected-(IC3-NC2-Pad2)") (class "Default")
      (node (ref "IC3") (pin "2") (pinfunction "NC2_2") (pintype "bidirectional"))
    )
    (net (code "105") (name "unconnected-(IC3-NC3-Pad3)") (class "Default")
      (node (ref "IC3") (pin "3") (pinfunction "NC3_3") (pintype "bidirectional"))
    )
    (net (code "106") (name "unconnected-(IC3-NC7-Pad7)") (class "Default")
      (node (ref "IC3") (pin "7") (pinfunction "NC7_7") (pintype "bidirectional"))
    )
    (net (code "107") (name "unconnected-(MOD1-5V-USB-Pad3)") (class "Default")
      (node (ref "MOD1") (pin "3") (pinfunction "5V-USB_3") (pintype "bidirectional"))
    )
    (net (code "108") (name "unconnected-(MOD1-SCL2-Pad29)") (class "Default")
      (node (ref "MOD1") (pin "29") (pinfunction "SCL2_29") (pintype "bidirectional"))
    )
    (net (code "109") (name "unconnected-(MOD1-SDA2-Pad30)") (class "Default")
      (node (ref "MOD1") (pin "30") (pinfunction "SDA2_30") (pintype "bidirectional"))
    )
  )
)
